# USB_CONNECTOR.net
KiCad netlist of a schematic drawn in Altium Designer
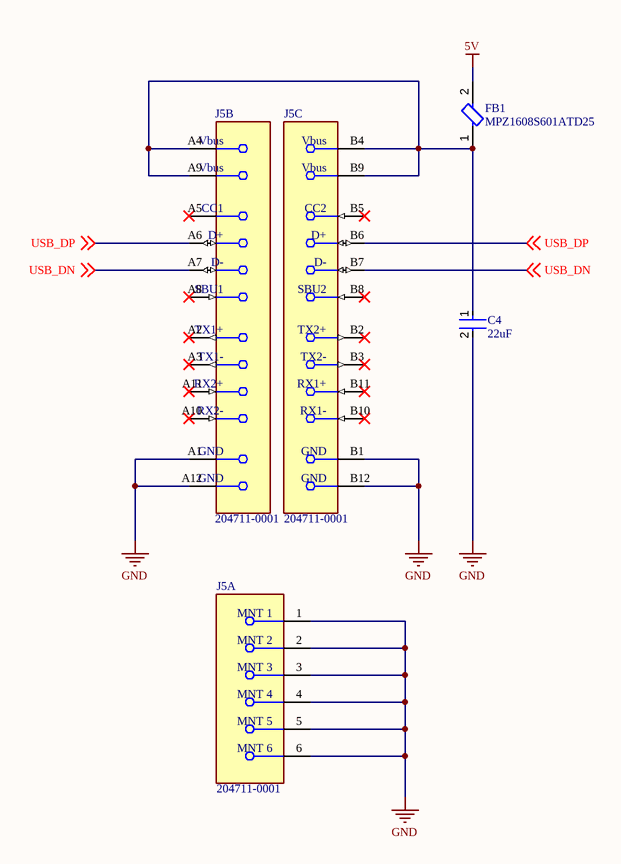
[diagram p0: USB_CONNECTOR.SchDoc]

(export (version "E")
  (design (tool "Eeschema 10.0.6"))
  (components
    (comp (ref "C4")
      (value "22uF")
      (footprint "FP-CL10-IPC_B")
      (description "Cap Ceramic 22uF 10V X5R ±20% Pad SMD 0603 +85°C T/R")
      (fields (field (name "TOLERANCE") "20%"))
      (libsource (lib "Altium Content Vault") (part "b4654b650e69147ec39a6b967a45e02"))
    )
    (comp (ref "FB1")
      (value "MPZ1608S601ATD25")
      (footprint "FP-MPZ1608-0_8-IPC_B")
      (description "Power line Ferrite Bead 600Ω @ 100MHz 1A DCR 0.15Ω AEC-Q200 SMD 0603")
      (fields (field (name "TOLERANCE") "25%"))
      (libsource (lib "Altium Content Vault") (part "5f30dd21d616792df468990f7003faa"))
    )
    (comp (ref "J5")
      (value "204711-0001")
      (footprint "FP-204711-0001-MFG")
      (description "USB VERTICAL TYPE C 3.1")
      (libsource (lib "Altium Content Vault") (part "b295db2379a271355c8cebff2fed634"))
    )
  )
  (nets
    (net (code "1") (name "5V") (class "Default")
      (node (ref "FB1") (pin "2") (pinfunction "2_2") (pintype "passive"))
    )
    (net (code "2") (name "GND") (class "Default")
      (node (ref "C4") (pin "2") (pinfunction "2_2") (pintype "passive"))
      (node (ref "J5") (pin "1") (pinfunction "MNT_1_1") (pintype "passive"))
      (node (ref "J5") (pin "2") (pinfunction "MNT_2_2") (pintype "passive"))
      (node (ref "J5") (pin "3") (pinfunction "MNT_3_3") (pintype "passive"))
      (node (ref "J5") (pin "4") (pinfunction "MNT_4_4") (pintype "passive"))
      (node (ref "J5") (pin "5") (pinfunction "MNT_5_5") (pintype "passive"))
      (node (ref "J5") (pin "6") (pinfunction "MNT_6_6") (pintype "passive"))
      (node (ref "J5") (pin "A1") (pinfunction "GND_A1") (pintype "power_in"))
      (node (ref "J5") (pin "A12") (pinfunction "GND_A12") (pintype "power_in"))
      (node (ref "J5") (pin "B1") (pinfunction "GND_B1") (pintype "power_in"))
      (node (ref "J5") (pin "B12") (pinfunction "GND_B12") (pintype "power_in"))
    )
    (net (code "3") (name "Net-(C4-Pad1)") (class "Default")
      (node (ref "C4") (pin "1") (pinfunction "1_1") (pintype "passive"))
      (node (ref "FB1") (pin "1") (pinfunction "1_1") (pintype "passive"))
      (node (ref "J5") (pin "A4") (pinfunction "Vbus_A4") (pintype "power_in"))
      (node (ref "J5") (pin "A9") (pinfunction "Vbus_A9") (pintype "power_in"))
      (node (ref "J5") (pin "B4") (pinfunction "Vbus_B4") (pintype "power_in"))
      (node (ref "J5") (pin "B9") (pinfunction "Vbus_B9") (pintype "power_in"))
    )
    (net (code "4") (name "USB_DN") (class "Default")
      (node (ref "J5") (pin "A7") (pinfunction "D-_A7") (pintype "bidirectional"))
      (node (ref "J5") (pin "B7") (pinfunction "D-_B7") (pintype "bidirectional"))
    )
    (net (code "5") (name "USB_DP") (class "Default")
      (node (ref "J5") (pin "A6") (pinfunction "D+_A6") (pintype "bidirectional"))
      (node (ref "J5") (pin "B6") (pinfunction "D+_B6") (pintype "bidirectional"))
    )
    (net (code "6") (name "unconnected-(J5B-CC1-PadA5)") (class "Default")
      (node (ref "J5") (pin "A5") (pinfunction "CC1_A5") (pintype "passive+no_connect"))
    )
    (net (code "7") (name "unconnected-(J5B-RX2+-PadA11)") (class "Default")
      (node (ref "J5") (pin "A11") (pinfunction "RX2+_A11") (pintype "input+no_connect"))
    )
    (net (code "8") (name "unconnected-(J5B-RX2--PadA10)") (class "Default")
      (node (ref "J5") (pin "A10") (pinfunction "RX2-_A10") (pintype "input+no_connect"))
    )
    (net (code "9") (name "unconnected-(J5B-SBU1-PadA8)") (class "Default")
      (node (ref "J5") (pin "A8") (pinfunction "SBU1_A8") (pintype "input+no_connect"))
    )
    (net (code "10") (name "unconnected-(J5B-TX1+-PadA2)") (class "Default")
      (node (ref "J5") (pin "A2") (pinfunction "TX1+_A2") (pintype "output+no_connect"))
    )
    (net (code "11") (name "unconnected-(J5B-TX1--PadA3)") (class "Default")
      (node (ref "J5") (pin "A3") (pinfunction "TX1-_A3") (pintype "output+no_connect"))
    )
    (net (code "12") (name "unconnected-(J5C-CC2-PadB5)") (class "Default")
      (node (ref "J5") (pin "B5") (pinfunction "CC2_B5") (pintype "input+no_connect"))
    )
    (net (code "13") (name "unconnected-(J5C-RX1+-PadB11)") (class "Default")
      (node (ref "J5") (pin "B11") (pinfunction "RX1+_B11") (pintype "input+no_connect"))
    )
    (net (code "14") (name "unconnected-(J5C-RX1--PadB10)") (class "Default")
      (node (ref "J5") (pin "B10") (pinfunction "RX1-_B10") (pintype "input+no_connect"))
    )
    (net (code "15") (name "unconnected-(J5C-SBU2-PadB8)") (class "Default")
      (node (ref "J5") (pin "B8") (pinfunction "SBU2_B8") (pintype "input+no_connect"))
    )
    (net (code "16") (name "unconnected-(J5C-TX2+-PadB2)") (class "Default")
      (node (ref "J5") (pin "B2") (pinfunction "TX2+_B2") (pintype "output+no_connect"))
    )
    (net (code "17") (name "unconnected-(J5C-TX2--PadB3)") (class "Default")
      (node (ref "J5") (pin "B3") (pinfunction "TX2-_B3") (pintype "output+no_connect"))
    )
  )
)
